# rele.net
KiCad netlist of a schematic drawn in Altium Designer
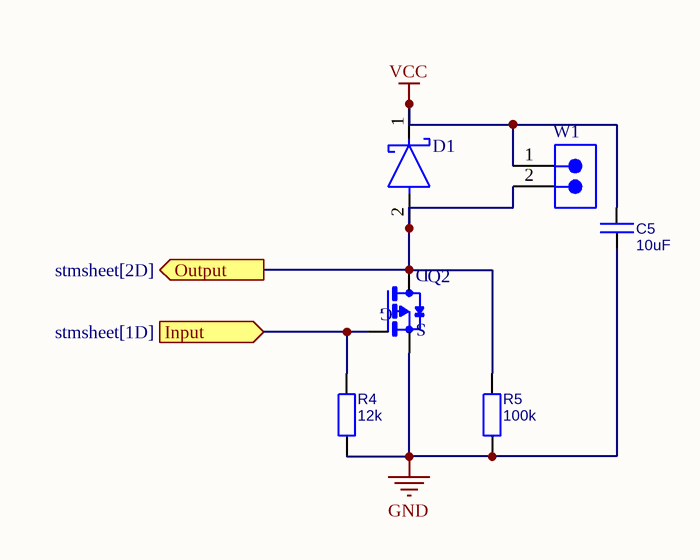
[diagram p0: rele.SchDoc]

(export (version "E")
  (design (tool "Eeschema 10.0.6"))
  (components
    (comp (ref "C5")
      (value "10uF")
      (footprint "C0603")
      (description "Capacitor")
      (libsource (lib "General") (part "C"))
    )
    (comp (ref "D1")
      (value "STPS0560Z")
      (footprint "FP-SOD-123-MFG")
      (description "DIODE SCHOTTKY 60V 500MA SOD123")
      (libsource (lib "Altium Content Vault") (part "1d6ec82d83fb6aee721767c19dac4b9"))
    )
    (comp (ref "Q2")
      (value "SI2323DS-T1-GE3")
      (footprint "SOT23")
      (description "P-Channel 20V 3.7A (Ta) 750mW (Ta) Surface Mount SOT-23-3 (TO-236)")
      (fields (field (name "MF") "Vishay"))
      (libsource (lib "SI2323DS-T1-GE3") (part "SI2323DS-T1-GE3"))
    )
    (comp (ref "R4")
      (value "12k")
      (footprint "R0603")
      (description "R")
      (libsource (lib "General") (part "R"))
    )
    (comp (ref "R5")
      (value "100k")
      (footprint "R0603")
      (description "R")
      (libsource (lib "General") (part "R"))
    )
    (comp (ref "W1")
      (value "~")
      (footprint "691321100002")
      (fields (field (name "VOLTAGE") "300V"))
      (libsource (lib "Altium Content Vault") (part "TBL - 1R - 02P - Male"))
    )
  )
  (nets
    (net (code "1") (name "/Input") (class "Default")
      (node (ref "Q2") (pin "1") (pinfunction "G_1") (pintype "passive"))
      (node (ref "R4") (pin "1") (pintype "passive"))
    )
    (net (code "2") (name "/Output") (class "Default")
      (node (ref "D1") (pin "2") (pinfunction "A_2") (pintype "passive"))
      (node (ref "Q2") (pin "3") (pinfunction "D_3") (pintype "passive"))
      (node (ref "R5") (pin "1") (pintype "passive"))
      (node (ref "W1") (pin "2") (pinfunction "2_2") (pintype "passive"))
    )
    (net (code "3") (name "GND") (class "Default")
      (node (ref "C5") (pin "2") (pinfunction "2_2") (pintype "passive"))
      (node (ref "Q2") (pin "2") (pinfunction "S_2") (pintype "passive"))
      (node (ref "R4") (pin "2") (pintype "passive"))
      (node (ref "R5") (pin "2") (pintype "passive"))
    )
    (net (code "4") (name "VCC") (class "Default")
      (node (ref "C5") (pin "1") (pinfunction "1_1") (pintype "passive"))
      (node (ref "D1") (pin "1") (pinfunction "C_1") (pintype "passive"))
      (node (ref "W1") (pin "1") (pinfunction "1_1") (pintype "passive"))
    )
  )
)
